# Keyboard.net
KiCad netlist of a schematic drawn in EAGLE
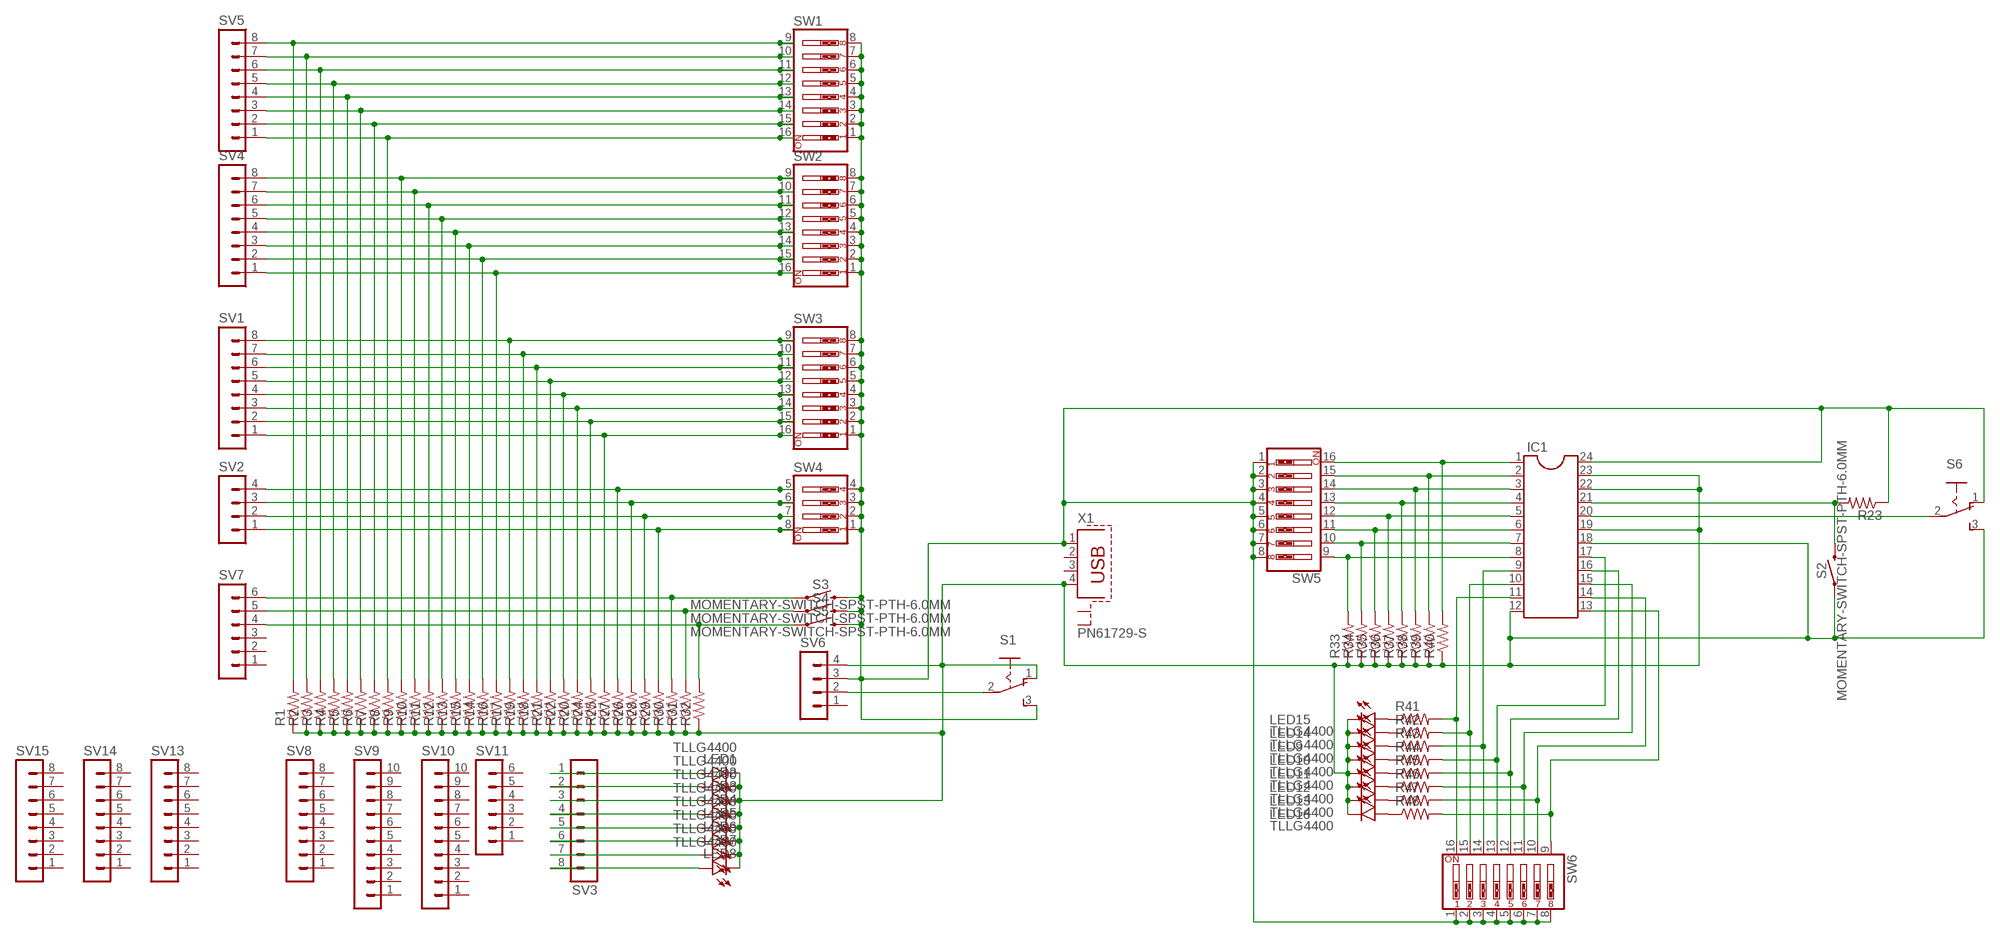
[diagram p0: schematic, sheet 1]

(export (version "E")
  (design (tool "Eeschema 10.0.6"))
  (components
    (comp (ref "IC1")
      (value "DIL24-6")
      (footprint "eagle-import:DIL24-6")
      (libsource (lib "eagle-import") (part "DIL24-6"))
    )
    (comp (ref "LED1")
      (value "TLLG4400")
      (footprint "eagle-import:LED3MM")
      (fields (field (name "MF") "VISHAY SEMICONDUCTOR"))
      (libsource (lib "eagle-import") (part "TLLG4400"))
    )
    (comp (ref "LED2")
      (value "TLLG4400")
      (footprint "eagle-import:LED3MM")
      (fields (field (name "MF") "VISHAY SEMICONDUCTOR"))
      (libsource (lib "eagle-import") (part "TLLG4400"))
    )
    (comp (ref "LED3")
      (value "TLLG4400")
      (footprint "eagle-import:LED3MM")
      (fields (field (name "MF") "VISHAY SEMICONDUCTOR"))
      (libsource (lib "eagle-import") (part "TLLG4400"))
    )
    (comp (ref "LED4")
      (value "TLLG4400")
      (footprint "eagle-import:LED3MM")
      (fields (field (name "MF") "VISHAY SEMICONDUCTOR"))
      (libsource (lib "eagle-import") (part "TLLG4400"))
    )
    (comp (ref "LED5")
      (value "TLLG4400")
      (footprint "eagle-import:LED3MM")
      (fields (field (name "MF") "VISHAY SEMICONDUCTOR"))
      (libsource (lib "eagle-import") (part "TLLG4400"))
    )
    (comp (ref "LED6")
      (value "TLLG4400")
      (footprint "eagle-import:LED3MM")
      (fields (field (name "MF") "VISHAY SEMICONDUCTOR"))
      (libsource (lib "eagle-import") (part "TLLG4400"))
    )
    (comp (ref "LED7")
      (value "TLLG4400")
      (footprint "eagle-import:LED3MM")
      (fields (field (name "MF") "VISHAY SEMICONDUCTOR"))
      (libsource (lib "eagle-import") (part "TLLG4400"))
    )
    (comp (ref "LED8")
      (value "TLLG4400")
      (footprint "eagle-import:LED3MM")
      (fields (field (name "MF") "VISHAY SEMICONDUCTOR"))
      (libsource (lib "eagle-import") (part "TLLG4400"))
    )
    (comp (ref "LED9")
      (value "TLLG4400")
      (footprint "eagle-import:LED3MM")
      (fields (field (name "MF") "VISHAY SEMICONDUCTOR"))
      (libsource (lib "eagle-import") (part "TLLG4400"))
    )
    (comp (ref "LED10")
      (value "TLLG4400")
      (footprint "eagle-import:LED3MM")
      (fields (field (name "MF") "VISHAY SEMICONDUCTOR"))
      (libsource (lib "eagle-import") (part "TLLG4400"))
    )
    (comp (ref "LED11")
      (value "TLLG4400")
      (footprint "eagle-import:LED3MM")
      (fields (field (name "MF") "VISHAY SEMICONDUCTOR"))
      (libsource (lib "eagle-import") (part "TLLG4400"))
    )
    (comp (ref "LED12")
      (value "TLLG4400")
      (footprint "eagle-import:LED3MM")
      (fields (field (name "MF") "VISHAY SEMICONDUCTOR"))
      (libsource (lib "eagle-import") (part "TLLG4400"))
    )
    (comp (ref "LED13")
      (value "TLLG4400")
      (footprint "eagle-import:LED3MM")
      (fields (field (name "MF") "VISHAY SEMICONDUCTOR"))
      (libsource (lib "eagle-import") (part "TLLG4400"))
    )
    (comp (ref "LED14")
      (value "TLLG4400")
      (footprint "eagle-import:LED3MM")
      (fields (field (name "MF") "VISHAY SEMICONDUCTOR"))
      (libsource (lib "eagle-import") (part "TLLG4400"))
    )
    (comp (ref "LED15")
      (value "TLLG4400")
      (footprint "eagle-import:LED3MM")
      (fields (field (name "MF") "VISHAY SEMICONDUCTOR"))
      (libsource (lib "eagle-import") (part "TLLG4400"))
    )
    (comp (ref "LED16")
      (value "TLLG4400")
      (footprint "eagle-import:LED3MM")
      (fields (field (name "MF") "VISHAY SEMICONDUCTOR"))
      (libsource (lib "eagle-import") (part "TLLG4400"))
    )
    (comp (ref "R1")
      (value "R-US_0207/2V")
      (footprint "eagle-import:0207_2V")
      (libsource (lib "eagle-import") (part "R-US_0207/2V"))
    )
    (comp (ref "R2")
      (value "R-US_0207/2V")
      (footprint "eagle-import:0207_2V")
      (libsource (lib "eagle-import") (part "R-US_0207/2V"))
    )
    (comp (ref "R3")
      (value "R-US_0207/2V")
      (footprint "eagle-import:0207_2V")
      (libsource (lib "eagle-import") (part "R-US_0207/2V"))
    )
    (comp (ref "R4")
      (value "R-US_0207/2V")
      (footprint "eagle-import:0207_2V")
      (libsource (lib "eagle-import") (part "R-US_0207/2V"))
    )
    (comp (ref "R5")
      (value "R-US_0207/2V")
      (footprint "eagle-import:0207_2V")
      (libsource (lib "eagle-import") (part "R-US_0207/2V"))
    )
    (comp (ref "R6")
      (value "R-US_0207/2V")
      (footprint "eagle-import:0207_2V")
      (libsource (lib "eagle-import") (part "R-US_0207/2V"))
    )
    (comp (ref "R7")
      (value "R-US_0207/2V")
      (footprint "eagle-import:0207_2V")
      (libsource (lib "eagle-import") (part "R-US_0207/2V"))
    )
    (comp (ref "R8")
      (value "R-US_0207/2V")
      (footprint "eagle-import:0207_2V")
      (libsource (lib "eagle-import") (part "R-US_0207/2V"))
    )
    (comp (ref "R9")
      (value "R-US_0207/2V")
      (footprint "eagle-import:0207_2V")
      (libsource (lib "eagle-import") (part "R-US_0207/2V"))
    )
    (comp (ref "R10")
      (value "R-US_0207/2V")
      (footprint "eagle-import:0207_2V")
      (libsource (lib "eagle-import") (part "R-US_0207/2V"))
    )
    (comp (ref "R11")
      (value "R-US_0207/2V")
      (footprint "eagle-import:0207_2V")
      (libsource (lib "eagle-import") (part "R-US_0207/2V"))
    )
    (comp (ref "R12")
      (value "R-US_0207/2V")
      (footprint "eagle-import:0207_2V")
      (libsource (lib "eagle-import") (part "R-US_0207/2V"))
    )
    (comp (ref "R13")
      (value "R-US_0207/2V")
      (footprint "eagle-import:0207_2V")
      (libsource (lib "eagle-import") (part "R-US_0207/2V"))
    )
    (comp (ref "R14")
      (value "R-US_0207/2V")
      (footprint "eagle-import:0207_2V")
      (libsource (lib "eagle-import") (part "R-US_0207/2V"))
    )
    (comp (ref "R15")
      (value "R-US_0207/2V")
      (footprint "eagle-import:0207_2V")
      (libsource (lib "eagle-import") (part "R-US_0207/2V"))
    )
    (comp (ref "R16")
      (value "R-US_0207/2V")
      (footprint "eagle-import:0207_2V")
      (libsource (lib "eagle-import") (part "R-US_0207/2V"))
    )
    (comp (ref "R17")
      (value "R-US_0207/2V")
      (footprint "eagle-import:0207_2V")
      (libsource (lib "eagle-import") (part "R-US_0207/2V"))
    )
    (comp (ref "R18")
      (value "R-US_0207/2V")
      (footprint "eagle-import:0207_2V")
      (libsource (lib "eagle-import") (part "R-US_0207/2V"))
    )
    (comp (ref "R19")
      (value "R-US_0207/2V")
      (footprint "eagle-import:0207_2V")
      (libsource (lib "eagle-import") (part "R-US_0207/2V"))
    )
    (comp (ref "R20")
      (value "R-US_0207/2V")
      (footprint "eagle-import:0207_2V")
      (libsource (lib "eagle-import") (part "R-US_0207/2V"))
    )
    (comp (ref "R21")
      (value "R-US_0207/2V")
      (footprint "eagle-import:0207_2V")
      (libsource (lib "eagle-import") (part "R-US_0207/2V"))
    )
    (comp (ref "R22")
      (value "R-US_0207/2V")
      (footprint "eagle-import:0207_2V")
      (libsource (lib "eagle-import") (part "R-US_0207/2V"))
    )
    (comp (ref "R23")
      (value "R-US_0207/2V")
      (footprint "eagle-import:0207_2V")
      (libsource (lib "eagle-import") (part "R-US_0207/2V"))
    )
    (comp (ref "R24")
      (value "R-US_0207/2V")
      (footprint "eagle-import:0207_2V")
      (libsource (lib "eagle-import") (part "R-US_0207/2V"))
    )
    (comp (ref "R25")
      (value "R-US_0207/2V")
      (footprint "eagle-import:0207_2V")
      (libsource (lib "eagle-import") (part "R-US_0207/2V"))
    )
    (comp (ref "R26")
      (value "R-US_0207/2V")
      (footprint "eagle-import:0207_2V")
      (libsource (lib "eagle-import") (part "R-US_0207/2V"))
    )
    (comp (ref "R27")
      (value "R-US_0207/2V")
      (footprint "eagle-import:0207_2V")
      (libsource (lib "eagle-import") (part "R-US_0207/2V"))
    )
    (comp (ref "R28")
      (value "R-US_0207/2V")
      (footprint "eagle-import:0207_2V")
      (libsource (lib "eagle-import") (part "R-US_0207/2V"))
    )
    (comp (ref "R29")
      (value "R-US_0207/2V")
      (footprint "eagle-import:0207_2V")
      (libsource (lib "eagle-import") (part "R-US_0207/2V"))
    )
    (comp (ref "R30")
      (value "R-US_0207/2V")
      (footprint "eagle-import:0207_2V")
      (libsource (lib "eagle-import") (part "R-US_0207/2V"))
    )
    (comp (ref "R31")
      (value "R-US_0207/2V")
      (footprint "eagle-import:0207_2V")
      (libsource (lib "eagle-import") (part "R-US_0207/2V"))
    )
    (comp (ref "R32")
      (value "R-US_0207/2V")
      (footprint "eagle-import:0207_2V")
      (libsource (lib "eagle-import") (part "R-US_0207/2V"))
    )
    (comp (ref "R33")
      (value "R-US_0207/2V")
      (footprint "eagle-import:0207_2V")
      (libsource (lib "eagle-import") (part "R-US_0207/2V"))
    )
    (comp (ref "R34")
      (value "R-US_0207/2V")
      (footprint "eagle-import:0207_2V")
      (libsource (lib "eagle-import") (part "R-US_0207/2V"))
    )
    (comp (ref "R35")
      (value "R-US_0207/2V")
      (footprint "eagle-import:0207_2V")
      (libsource (lib "eagle-import") (part "R-US_0207/2V"))
    )
    (comp (ref "R36")
      (value "R-US_0207/2V")
      (footprint "eagle-import:0207_2V")
      (libsource (lib "eagle-import") (part "R-US_0207/2V"))
    )
    (comp (ref "R37")
      (value "R-US_0207/2V")
      (footprint "eagle-import:0207_2V")
      (libsource (lib "eagle-import") (part "R-US_0207/2V"))
    )
    (comp (ref "R38")
      (value "R-US_0207/2V")
      (footprint "eagle-import:0207_2V")
      (libsource (lib "eagle-import") (part "R-US_0207/2V"))
    )
    (comp (ref "R39")
      (value "R-US_0207/2V")
      (footprint "eagle-import:0207_2V")
      (libsource (lib "eagle-import") (part "R-US_0207/2V"))
    )
    (comp (ref "R40")
      (value "R-US_0207/2V")
      (footprint "eagle-import:0207_2V")
      (libsource (lib "eagle-import") (part "R-US_0207/2V"))
    )
    (comp (ref "R41")
      (value "R-US_0207/2V")
      (footprint "eagle-import:0207_2V")
      (libsource (lib "eagle-import") (part "R-US_0207/2V"))
    )
    (comp (ref "R42")
      (value "R-US_0207/2V")
      (footprint "eagle-import:0207_2V")
      (libsource (lib "eagle-import") (part "R-US_0207/2V"))
    )
    (comp (ref "R43")
      (value "R-US_0207/2V")
      (footprint "eagle-import:0207_2V")
      (libsource (lib "eagle-import") (part "R-US_0207/2V"))
    )
    (comp (ref "R44")
      (value "R-US_0207/2V")
      (footprint "eagle-import:0207_2V")
      (libsource (lib "eagle-import") (part "R-US_0207/2V"))
    )
    (comp (ref "R45")
      (value "R-US_0207/2V")
      (footprint "eagle-import:0207_2V")
      (libsource (lib "eagle-import") (part "R-US_0207/2V"))
    )
    (comp (ref "R46")
      (value "R-US_0207/2V")
      (footprint "eagle-import:0207_2V")
      (libsource (lib "eagle-import") (part "R-US_0207/2V"))
    )
    (comp (ref "R47")
      (value "R-US_0207/2V")
      (footprint "eagle-import:0207_2V")
      (libsource (lib "eagle-import") (part "R-US_0207/2V"))
    )
    (comp (ref "R48")
      (value "R-US_0207/2V")
      (footprint "eagle-import:0207_2V")
      (libsource (lib "eagle-import") (part "R-US_0207/2V"))
    )
    (comp (ref "S1")
      (value "M251")
      (footprint "eagle-import:M251")
      (libsource (lib "eagle-import") (part "M251"))
    )
    (comp (ref "S2")
      (value "MOMENTARY-SWITCH-SPST-PTH-6.0MM")
      (footprint "eagle-import:TACTILE_SWITCH_PTH_6.0MM")
      (libsource (lib "eagle-import") (part "MOMENTARY-SWITCH-SPST-PTH-6.0MM"))
    )
    (comp (ref "S3")
      (value "MOMENTARY-SWITCH-SPST-PTH-6.0MM")
      (footprint "eagle-import:TACTILE_SWITCH_PTH_6.0MM")
      (libsource (lib "eagle-import") (part "MOMENTARY-SWITCH-SPST-PTH-6.0MM"))
    )
    (comp (ref "S4")
      (value "MOMENTARY-SWITCH-SPST-PTH-6.0MM")
      (footprint "eagle-import:TACTILE_SWITCH_PTH_6.0MM")
      (libsource (lib "eagle-import") (part "MOMENTARY-SWITCH-SPST-PTH-6.0MM"))
    )
    (comp (ref "S5")
      (value "MOMENTARY-SWITCH-SPST-PTH-6.0MM")
      (footprint "eagle-import:TACTILE_SWITCH_PTH_6.0MM")
      (libsource (lib "eagle-import") (part "MOMENTARY-SWITCH-SPST-PTH-6.0MM"))
    )
    (comp (ref "S6")
      (value "M251")
      (footprint "eagle-import:M251")
      (libsource (lib "eagle-import") (part "M251"))
    )
    (comp (ref "SV1")
      (value "MA08-1")
      (footprint "eagle-import:MA08-1")
      (libsource (lib "eagle-import") (part "MA08-1"))
    )
    (comp (ref "SV2")
      (value "MA04-1")
      (footprint "eagle-import:MA04-1")
      (libsource (lib "eagle-import") (part "MA04-1"))
    )
    (comp (ref "SV3")
      (value "MA08-1")
      (footprint "eagle-import:MA08-1")
      (libsource (lib "eagle-import") (part "MA08-1"))
    )
    (comp (ref "SV4")
      (value "MA08-1")
      (footprint "eagle-import:MA08-1")
      (libsource (lib "eagle-import") (part "MA08-1"))
    )
    (comp (ref "SV5")
      (value "MA08-1")
      (footprint "eagle-import:MA08-1")
      (libsource (lib "eagle-import") (part "MA08-1"))
    )
    (comp (ref "SV6")
      (value "MA04-1")
      (footprint "eagle-import:MA04-1")
      (libsource (lib "eagle-import") (part "MA04-1"))
    )
    (comp (ref "SV7")
      (value "MA06-1")
      (footprint "eagle-import:MA06-1")
      (libsource (lib "eagle-import") (part "MA06-1"))
    )
    (comp (ref "SV8")
      (value "MA08-1")
      (footprint "eagle-import:MA08-1")
      (libsource (lib "eagle-import") (part "MA08-1"))
    )
    (comp (ref "SV9")
      (value "MA10-1")
      (footprint "eagle-import:MA10-1")
      (libsource (lib "eagle-import") (part "MA10-1"))
    )
    (comp (ref "SV10")
      (value "MA10-1")
      (footprint "eagle-import:MA10-1")
      (libsource (lib "eagle-import") (part "MA10-1"))
    )
    (comp (ref "SV11")
      (value "MA06-1")
      (footprint "eagle-import:MA06-1")
      (libsource (lib "eagle-import") (part "MA06-1"))
    )
    (comp (ref "SV13")
      (value "MA08-1")
      (footprint "eagle-import:MA08-1")
      (libsource (lib "eagle-import") (part "MA08-1"))
    )
    (comp (ref "SV14")
      (value "MA08-1")
      (footprint "eagle-import:MA08-1")
      (libsource (lib "eagle-import") (part "MA08-1"))
    )
    (comp (ref "SV15")
      (value "MA08-1")
      (footprint "eagle-import:MA08-1")
      (libsource (lib "eagle-import") (part "MA08-1"))
    )
    (comp (ref "SW1")
      (value "SW_DIP-8")
      (footprint "eagle-import:EDG-08")
      (libsource (lib "eagle-import") (part "SW_DIP-8"))
    )
    (comp (ref "SW2")
      (value "SW_DIP-8")
      (footprint "eagle-import:EDG-08")
      (libsource (lib "eagle-import") (part "SW_DIP-8"))
    )
    (comp (ref "SW3")
      (value "SW_DIP-8")
      (footprint "eagle-import:EDG-08")
      (libsource (lib "eagle-import") (part "SW_DIP-8"))
    )
    (comp (ref "SW4")
      (value "SW_DIP-4")
      (footprint "eagle-import:EDG-04")
      (libsource (lib "eagle-import") (part "SW_DIP-4"))
    )
    (comp (ref "SW5")
      (value "SW_DIP-8")
      (footprint "eagle-import:EDG-08")
      (libsource (lib "eagle-import") (part "SW_DIP-8"))
    )
    (comp (ref "SW6")
      (value "SW_DIP-8")
      (footprint "eagle-import:EDG-08")
      (libsource (lib "eagle-import") (part "SW_DIP-8"))
    )
    (comp (ref "X1")
      (value "PN61729-S")
      (footprint "eagle-import:PN61729-S")
      (libsource (lib "eagle-import") (part "PN61729-S"))
    )
  )
  (nets
    (net (code "1") (name "Net-(IC1-Pad1)") (class "Default")
      (node (ref "IC1") (pin "1") (pinfunction "1_1") (pintype "passive"))
      (node (ref "R40") (pin "2") (pinfunction "2_2") (pintype "passive"))
      (node (ref "SW5") (pin "16") (pinfunction "16_16") (pintype "passive"))
    )
    (net (code "2") (name "Net-(IC1-Pad2)") (class "Default")
      (node (ref "IC1") (pin "2") (pinfunction "2_2") (pintype "passive"))
      (node (ref "R39") (pin "2") (pinfunction "2_2") (pintype "passive"))
      (node (ref "SW5") (pin "15") (pinfunction "15_15") (pintype "passive"))
    )
    (net (code "3") (name "Net-(IC1-Pad3)") (class "Default")
      (node (ref "IC1") (pin "3") (pinfunction "3_3") (pintype "passive"))
      (node (ref "R38") (pin "2") (pinfunction "2_2") (pintype "passive"))
      (node (ref "SW5") (pin "14") (pinfunction "14_14") (pintype "passive"))
    )
    (net (code "4") (name "Net-(IC1-Pad4)") (class "Default")
      (node (ref "IC1") (pin "4") (pinfunction "4_4") (pintype "passive"))
      (node (ref "R37") (pin "2") (pinfunction "2_2") (pintype "passive"))
      (node (ref "SW5") (pin "13") (pinfunction "13_13") (pintype "passive"))
    )
    (net (code "5") (name "Net-(IC1-Pad5)") (class "Default")
      (node (ref "IC1") (pin "5") (pinfunction "5_5") (pintype "passive"))
      (node (ref "R36") (pin "2") (pinfunction "2_2") (pintype "passive"))
      (node (ref "SW5") (pin "12") (pinfunction "12_12") (pintype "passive"))
    )
    (net (code "6") (name "Net-(IC1-Pad6)") (class "Default")
      (node (ref "IC1") (pin "6") (pinfunction "6_6") (pintype "passive"))
      (node (ref "R35") (pin "2") (pinfunction "2_2") (pintype "passive"))
      (node (ref "SW5") (pin "11") (pinfunction "11_11") (pintype "passive"))
    )
    (net (code "7") (name "Net-(IC1-Pad7)") (class "Default")
      (node (ref "IC1") (pin "7") (pinfunction "7_7") (pintype "passive"))
      (node (ref "R34") (pin "2") (pinfunction "2_2") (pintype "passive"))
      (node (ref "SW5") (pin "10") (pinfunction "10_10") (pintype "passive"))
    )
    (net (code "8") (name "Net-(IC1-Pad8)") (class "Default")
      (node (ref "IC1") (pin "8") (pinfunction "8_8") (pintype "passive"))
      (node (ref "R33") (pin "2") (pinfunction "2_2") (pintype "passive"))
      (node (ref "SW5") (pin "9") (pinfunction "9_9") (pintype "passive"))
    )
    (net (code "9") (name "Net-(IC1-Pad9)") (class "Default")
      (node (ref "IC1") (pin "9") (pinfunction "9_9") (pintype "passive"))
      (node (ref "R43") (pin "2") (pinfunction "2_2") (pintype "passive"))
      (node (ref "SW6") (pin "14") (pinfunction "14_14") (pintype "passive"))
    )
    (net (code "10") (name "Net-(IC1-Pad10)") (class "Default")
      (node (ref "IC1") (pin "10") (pinfunction "10_10") (pintype "passive"))
      (node (ref "R42") (pin "2") (pinfunction "2_2") (pintype "passive"))
      (node (ref "SW6") (pin "15") (pinfunction "15_15") (pintype "passive"))
    )
    (net (code "11") (name "Net-(IC1-Pad11)") (class "Default")
      (node (ref "IC1") (pin "11") (pinfunction "11_11") (pintype "passive"))
      (node (ref "R41") (pin "2") (pinfunction "2_2") (pintype "passive"))
      (node (ref "SW6") (pin "16") (pinfunction "16_16") (pintype "passive"))
    )
    (net (code "12") (name "Net-(IC1-Pad13)") (class "Default")
      (node (ref "IC1") (pin "13") (pinfunction "13_13") (pintype "passive"))
      (node (ref "R48") (pin "2") (pinfunction "2_2") (pintype "passive"))
      (node (ref "SW6") (pin "9") (pinfunction "9_9") (pintype "passive"))
    )
    (net (code "13") (name "Net-(IC1-Pad14)") (class "Default")
      (node (ref "IC1") (pin "14") (pinfunction "14_14") (pintype "passive"))
      (node (ref "R47") (pin "2") (pinfunction "2_2") (pintype "passive"))
      (node (ref "SW6") (pin "10") (pinfunction "10_10") (pintype "passive"))
    )
    (net (code "14") (name "Net-(IC1-Pad15)") (class "Default")
      (node (ref "IC1") (pin "15") (pinfunction "15_15") (pintype "passive"))
      (node (ref "R46") (pin "2") (pinfunction "2_2") (pintype "passive"))
      (node (ref "SW6") (pin "11") (pinfunction "11_11") (pintype "passive"))
    )
    (net (code "15") (name "Net-(IC1-Pad16)") (class "Default")
      (node (ref "IC1") (pin "16") (pinfunction "16_16") (pintype "passive"))
      (node (ref "R45") (pin "2") (pinfunction "2_2") (pintype "passive"))
      (node (ref "SW6") (pin "12") (pinfunction "12_12") (pintype "passive"))
    )
    (net (code "16") (name "Net-(IC1-Pad17)") (class "Default")
      (node (ref "IC1") (pin "17") (pinfunction "17_17") (pintype "passive"))
      (node (ref "R44") (pin "2") (pinfunction "2_2") (pintype "passive"))
      (node (ref "SW6") (pin "13") (pinfunction "13_13") (pintype "passive"))
    )
    (net (code "17") (name "Net-(LED1-C)") (class "Default")
      (node (ref "IC1") (pin "12") (pinfunction "12_12") (pintype "passive"))
      (node (ref "IC1") (pin "18") (pinfunction "18_18") (pintype "passive"))
      (node (ref "IC1") (pin "19") (pinfunction "19_19") (pintype "passive"))
      (node (ref "IC1") (pin "22") (pinfunction "22_22") (pintype "passive"))
      (node (ref "IC1") (pin "23") (pinfunction "23_23") (pintype "passive"))
      (node (ref "LED1") (pin "K") (pinfunction "C_K") (pintype "passive"))
      (node (ref "LED10") (pin "K") (pinfunction "C_K") (pintype "passive"))
      (node (ref "LED11") (pin "K") (pinfunction "C_K") (pintype "passive"))
      (node (ref "LED12") (pin "K") (pinfunction "C_K") (pintype "passive"))
      (node (ref "LED13") (pin "K") (pinfunction "C_K") (pintype "passive"))
      (node (ref "LED14") (pin "K") (pinfunction "C_K") (pintype "passive"))
      (node (ref "LED15") (pin "K") (pinfunction "C_K") (pintype "passive"))
      (node (ref "LED16") (pin "K") (pinfunction "C_K") (pintype "passive"))
      (node (ref "LED2") (pin "K") (pinfunction "C_K") (pintype "passive"))
      (node (ref "LED3") (pin "K") (pinfunction "C_K") (pintype "passive"))
      (node (ref "LED4") (pin "K") (pinfunction "C_K") (pintype "passive"))
      (node (ref "LED5") (pin "K") (pinfunction "C_K") (pintype "passive"))
      (node (ref "LED6") (pin "K") (pinfunction "C_K") (pintype "passive"))
      (node (ref "LED7") (pin "K") (pinfunction "C_K") (pintype "passive"))
      (node (ref "LED8") (pin "K") (pinfunction "C_K") (pintype "passive"))
      (node (ref "LED9") (pin "K") (pinfunction "C_K") (pintype "passive"))
      (node (ref "R1") (pin "1") (pinfunction "1_1") (pintype "passive"))
      (node (ref "R10") (pin "1") (pinfunction "1_1") (pintype "passive"))
      (node (ref "R11") (pin "1") (pinfunction "1_1") (pintype "passive"))
      (node (ref "R12") (pin "1") (pinfunction "1_1") (pintype "passive"))
      (node (ref "R13") (pin "1") (pinfunction "1_1") (pintype "passive"))
      (node (ref "R14") (pin "1") (pinfunction "1_1") (pintype "passive"))
      (node (ref "R15") (pin "1") (pinfunction "1_1") (pintype "passive"))
      (node (ref "R16") (pin "1") (pinfunction "1_1") (pintype "passive"))
      (node (ref "R17") (pin "1") (pinfunction "1_1") (pintype "passive"))
      (node (ref "R18") (pin "1") (pinfunction "1_1") (pintype "passive"))
      (node (ref "R19") (pin "1") (pinfunction "1_1") (pintype "passive"))
      (node (ref "R2") (pin "1") (pinfunction "1_1") (pintype "passive"))
      (node (ref "R20") (pin "1") (pinfunction "1_1") (pintype "passive"))
      (node (ref "R21") (pin "1") (pinfunction "1_1") (pintype "passive"))
      (node (ref "R22") (pin "1") (pinfunction "1_1") (pintype "passive"))
      (node (ref "R24") (pin "1") (pinfunction "1_1") (pintype "passive"))
      (node (ref "R25") (pin "1") (pinfunction "1_1") (pintype "passive"))
      (node (ref "R26") (pin "1") (pinfunction "1_1") (pintype "passive"))
      (node (ref "R27") (pin "1") (pinfunction "1_1") (pintype "passive"))
      (node (ref "R28") (pin "1") (pinfunction "1_1") (pintype "passive"))
      (node (ref "R29") (pin "1") (pinfunction "1_1") (pintype "passive"))
      (node (ref "R3") (pin "1") (pinfunction "1_1") (pintype "passive"))
      (node (ref "R30") (pin "1") (pinfunction "1_1") (pintype "passive"))
      (node (ref "R31") (pin "1") (pinfunction "1_1") (pintype "passive"))
      (node (ref "R32") (pin "1") (pinfunction "1_1") (pintype "passive"))
      (node (ref "R33") (pin "1") (pinfunction "1_1") (pintype "passive"))
      (node (ref "R34") (pin "1") (pinfunction "1_1") (pintype "passive"))
      (node (ref "R35") (pin "1") (pinfunction "1_1") (pintype "passive"))
      (node (ref "R36") (pin "1") (pinfunction "1_1") (pintype "passive"))
      (node (ref "R37") (pin "1") (pinfunction "1_1") (pintype "passive"))
      (node (ref "R38") (pin "1") (pinfunction "1_1") (pintype "passive"))
      (node (ref "R39") (pin "1") (pinfunction "1_1") (pintype "passive"))
      (node (ref "R4") (pin "1") (pinfunction "1_1") (pintype "passive"))
      (node (ref "R40") (pin "1") (pinfunction "1_1") (pintype "passive"))
      (node (ref "R5") (pin "1") (pinfunction "1_1") (pintype "passive"))
      (node (ref "R6") (pin "1") (pinfunction "1_1") (pintype "passive"))
      (node (ref "R7") (pin "1") (pinfunction "1_1") (pintype "passive"))
      (node (ref "R8") (pin "1") (pinfunction "1_1") (pintype "passive"))
      (node (ref "R9") (pin "1") (pinfunction "1_1") (pintype "passive"))
      (node (ref "S1") (pin "1") (pinfunction "O_1") (pintype "passive"))
      (node (ref "S2") (pin "1") (pinfunction "1_1") (pintype "passive"))
      (node (ref "S6") (pin "3") (pinfunction "S_3") (pintype "passive"))
      (node (ref "SV6") (pin "4") (pinfunction "4_4") (pintype "passive"))
      (node (ref "X1") (pin "4") (pinfunction "4_4") (pintype "passive"))
    )
    (net (code "18") (name "Net-(LED1-PadA)") (class "Default")
      (node (ref "LED1") (pin "A") (pinfunction "A_A") (pintype "passive"))
      (node (ref "SV3") (pin "1") (pinfunction "1_1") (pintype "passive"))
    )
    (net (code "19") (name "Net-(LED2-PadA)") (class "Default")
      (node (ref "LED2") (pin "A") (pinfunction "A_A") (pintype "passive"))
      (node (ref "SV3") (pin "2") (pinfunction "2_2") (pintype "passive"))
    )
    (net (code "20") (name "Net-(LED3-PadA)") (class "Default")
      (node (ref "LED3") (pin "A") (pinfunction "A_A") (pintype "passive"))
      (node (ref "SV3") (pin "3") (pinfunction "3_3") (pintype "passive"))
    )
    (net (code "21") (name "Net-(LED4-PadA)") (class "Default")
      (node (ref "LED4") (pin "A") (pinfunction "A_A") (pintype "passive"))
      (node (ref "SV3") (pin "4") (pinfunction "4_4") (pintype "passive"))
    )
    (net (code "22") (name "Net-(LED5-PadA)") (class "Default")
      (node (ref "LED5") (pin "A") (pinfunction "A_A") (pintype "passive"))
      (node (ref "SV3") (pin "5") (pinfunction "5_5") (pintype "passive"))
    )
    (net (code "23") (name "Net-(LED6-PadA)") (class "Default")
      (node (ref "LED6") (pin "A") (pinfunction "A_A") (pintype "passive"))
      (node (ref "SV3") (pin "6") (pinfunction "6_6") (pintype "passive"))
    )
    (net (code "24") (name "Net-(LED7-PadA)") (class "Default")
      (node (ref "LED7") (pin "A") (pinfunction "A_A") (pintype "passive"))
      (node (ref "SV3") (pin "7") (pinfunction "7_7") (pintype "passive"))
    )
    (net (code "25") (name "Net-(LED8-PadA)") (class "Default")
      (node (ref "LED8") (pin "A") (pinfunction "A_A") (pintype "passive"))
      (node (ref "SV3") (pin "8") (pinfunction "8_8") (pintype "passive"))
    )
    (net (code "26") (name "Net-(LED9-PadA)") (class "Default")
      (node (ref "LED9") (pin "A") (pinfunction "A_A") (pintype "passive"))
      (node (ref "R43") (pin "1") (pinfunction "1_1") (pintype "passive"))
    )
    (net (code "27") (name "Net-(LED10-PadA)") (class "Default")
      (node (ref "LED10") (pin "A") (pinfunction "A_A") (pintype "passive"))
      (node (ref "R44") (pin "1") (pinfunction "1_1") (pintype "passive"))
    )
    (net (code "28") (name "Net-(LED11-PadA)") (class "Default")
      (node (ref "LED11") (pin "A") (pinfunction "A_A") (pintype "passive"))
      (node (ref "R45") (pin "1") (pinfunction "1_1") (pintype "passive"))
    )
    (net (code "29") (name "Net-(LED12-PadA)") (class "Default")
      (node (ref "LED12") (pin "A") (pinfunction "A_A") (pintype "passive"))
      (node (ref "R46") (pin "1") (pinfunction "1_1") (pintype "passive"))
    )
    (net (code "30") (name "Net-(LED13-PadA)") (class "Default")
      (node (ref "LED13") (pin "A") (pinfunction "A_A") (pintype "passive"))
      (node (ref "R47") (pin "1") (pinfunction "1_1") (pintype "passive"))
    )
    (net (code "31") (name "Net-(LED14-PadA)") (class "Default")
      (node (ref "LED14") (pin "A") (pinfunction "A_A") (pintype "passive"))
      (node (ref "R42") (pin "1") (pinfunction "1_1") (pintype "passive"))
    )
    (net (code "32") (name "Net-(LED15-PadA)") (class "Default")
      (node (ref "LED15") (pin "A") (pinfunction "A_A") (pintype "passive"))
      (node (ref "R41") (pin "1") (pinfunction "1_1") (pintype "passive"))
    )
    (net (code "33") (name "Net-(LED16-PadA)") (class "Default")
      (node (ref "LED16") (pin "A") (pinfunction "A_A") (pintype "passive"))
      (node (ref "R48") (pin "1") (pinfunction "1_1") (pintype "passive"))
    )
    (net (code "34") (name "Net-(R1-Pad2)") (class "Default")
      (node (ref "R1") (pin "2") (pinfunction "2_2") (pintype "passive"))
      (node (ref "SV5") (pin "8") (pinfunction "8_8") (pintype "passive"))
      (node (ref "SW1") (pin "9") (pinfunction "9_9") (pintype "passive"))
    )
    (net (code "35") (name "Net-(R2-Pad2)") (class "Default")
      (node (ref "R2") (pin "2") (pinfunction "2_2") (pintype "passive"))
      (node (ref "SV5") (pin "7") (pinfunction "7_7") (pintype "passive"))
      (node (ref "SW1") (pin "10") (pinfunction "10_10") (pintype "passive"))
    )
    (net (code "36") (name "Net-(R3-Pad2)") (class "Default")
      (node (ref "R3") (pin "2") (pinfunction "2_2") (pintype "passive"))
      (node (ref "SV5") (pin "6") (pinfunction "6_6") (pintype "passive"))
      (node (ref "SW1") (pin "11") (pinfunction "11_11") (pintype "passive"))
    )
    (net (code "37") (name "Net-(R4-Pad2)") (class "Default")
      (node (ref "R4") (pin "2") (pinfunction "2_2") (pintype "passive"))
      (node (ref "SV5") (pin "5") (pinfunction "5_5") (pintype "passive"))
      (node (ref "SW1") (pin "12") (pinfunction "12_12") (pintype "passive"))
    )
    (net (code "38") (name "Net-(R5-Pad2)") (class "Default")
      (node (ref "R5") (pin "2") (pinfunction "2_2") (pintype "passive"))
      (node (ref "SV5") (pin "4") (pinfunction "4_4") (pintype "passive"))
      (node (ref "SW1") (pin "13") (pinfunction "13_13") (pintype "passive"))
    )
    (net (code "39") (name "Net-(R6-Pad2)") (class "Default")
      (node (ref "R6") (pin "2") (pinfunction "2_2") (pintype "passive"))
      (node (ref "SV5") (pin "3") (pinfunction "3_3") (pintype "passive"))
      (node (ref "SW1") (pin "14") (pinfunction "14_14") (pintype "passive"))
    )
    (net (code "40") (name "Net-(R7-Pad2)") (class "Default")
      (node (ref "R7") (pin "2") (pinfunction "2_2") (pintype "passive"))
      (node (ref "SV5") (pin "2") (pinfunction "2_2") (pintype "passive"))
      (node (ref "SW1") (pin "15") (pinfunction "15_15") (pintype "passive"))
    )
    (net (code "41") (name "Net-(R8-Pad2)") (class "Default")
      (node (ref "R8") (pin "2") (pinfunction "2_2") (pintype "passive"))
      (node (ref "SV5") (pin "1") (pinfunction "1_1") (pintype "passive"))
      (node (ref "SW1") (pin "16") (pinfunction "16_16") (pintype "passive"))
    )
    (net (code "42") (name "Net-(R9-Pad2)") (class "Default")
      (node (ref "R9") (pin "2") (pinfunction "2_2") (pintype "passive"))
      (node (ref "SV4") (pin "8") (pinfunction "8_8") (pintype "passive"))
      (node (ref "SW2") (pin "9") (pinfunction "9_9") (pintype "passive"))
    )
    (net (code "43") (name "Net-(R10-Pad2)") (class "Default")
      (node (ref "R10") (pin "2") (pinfunction "2_2") (pintype "passive"))
      (node (ref "SV4") (pin "7") (pinfunction "7_7") (pintype "passive"))
      (node (ref "SW2") (pin "10") (pinfunction "10_10") (pintype "passive"))
    )
    (net (code "44") (name "Net-(R11-Pad2)") (class "Default")
      (node (ref "R11") (pin "2") (pinfunction "2_2") (pintype "passive"))
      (node (ref "SV4") (pin "6") (pinfunction "6_6") (pintype "passive"))
      (node (ref "SW2") (pin "11") (pinfunction "11_11") (pintype "passive"))
    )
    (net (code "45") (name "Net-(R12-Pad2)") (class "Default")
      (node (ref "R12") (pin "2") (pinfunction "2_2") (pintype "passive"))
      (node (ref "SV4") (pin "5") (pinfunction "5_5") (pintype "passive"))
      (node (ref "SW2") (pin "12") (pinfunction "12_12") (pintype "passive"))
    )
    (net (code "46") (name "Net-(R13-Pad2)") (class "Default")
      (node (ref "R13") (pin "2") (pinfunction "2_2") (pintype "passive"))
      (node (ref "SV4") (pin "4") (pinfunction "4_4") (pintype "passive"))
      (node (ref "SW2") (pin "13") (pinfunction "13_13") (pintype "passive"))
    )
    (net (code "47") (name "Net-(R14-Pad2)") (class "Default")
      (node (ref "R14") (pin "2") (pinfunction "2_2") (pintype "passive"))
      (node (ref "SV4") (pin "2") (pinfunction "2_2") (pintype "passive"))
      (node (ref "SW2") (pin "15") (pinfunction "15_15") (pintype "passive"))
    )
    (net (code "48") (name "Net-(R15-Pad2)") (class "Default")
      (node (ref "R15") (pin "2") (pinfunction "2_2") (pintype "passive"))
      (node (ref "SV4") (pin "3") (pinfunction "3_3") (pintype "passive"))
      (node (ref "SW2") (pin "14") (pinfunction "14_14") (pintype "passive"))
    )
    (net (code "49") (name "Net-(R16-Pad2)") (class "Default")
      (node (ref "R16") (pin "2") (pinfunction "2_2") (pintype "passive"))
      (node (ref "SV4") (pin "1") (pinfunction "1_1") (pintype "passive"))
      (node (ref "SW2") (pin "16") (pinfunction "16_16") (pintype "passive"))
    )
    (net (code "50") (name "Net-(R17-Pad2)") (class "Default")
      (node (ref "R17") (pin "2") (pinfunction "2_2") (pintype "passive"))
      (node (ref "SV1") (pin "8") (pinfunction "8_8") (pintype "passive"))
      (node (ref "SW3") (pin "9") (pinfunction "9_9") (pintype "passive"))
    )
    (net (code "51") (name "Net-(R18-Pad2)") (class "Default")
      (node (ref "R18") (pin "2") (pinfunction "2_2") (pintype "passive"))
      (node (ref "SV1") (pin "6") (pinfunction "6_6") (pintype "passive"))
      (node (ref "SW3") (pin "11") (pinfunction "11_11") (pintype "passive"))
    )
    (net (code "52") (name "Net-(R19-Pad2)") (class "Default")
      (node (ref "R19") (pin "2") (pinfunction "2_2") (pintype "passive"))
      (node (ref "SV1") (pin "7") (pinfunction "7_7") (pintype "passive"))
      (node (ref "SW3") (pin "10") (pinfunction "10_10") (pintype "passive"))
    )
    (net (code "53") (name "Net-(R20-Pad2)") (class "Default")
      (node (ref "R20") (pin "2") (pinfunction "2_2") (pintype "passive"))
      (node (ref "SV1") (pin "3") (pinfunction "3_3") (pintype "passive"))
      (node (ref "SW3") (pin "14") (pinfunction "14_14") (pintype "passive"))
    )
    (net (code "54") (name "Net-(R21-Pad2)") (class "Default")
      (node (ref "R21") (pin "2") (pinfunction "2_2") (pintype "passive"))
      (node (ref "SV1") (pin "5") (pinfunction "5_5") (pintype "passive"))
      (node (ref "SW3") (pin "12") (pinfunction "12_12") (pintype "passive"))
    )
    (net (code "55") (name "Net-(R22-Pad2)") (class "Default")
      (node (ref "R22") (pin "2") (pinfunction "2_2") (pintype "passive"))
      (node (ref "SV1") (pin "4") (pinfunction "4_4") (pintype "passive"))
      (node (ref "SW3") (pin "13") (pinfunction "13_13") (pintype "passive"))
    )
    (net (code "56") (name "Net-(R24-Pad2)") (class "Default")
      (node (ref "R24") (pin "2") (pinfunction "2_2") (pintype "passive"))
      (node (ref "SV1") (pin "2") (pinfunction "2_2") (pintype "passive"))
      (node (ref "SW3") (pin "15") (pinfunction "15_15") (pintype "passive"))
    )
    (net (code "57") (name "Net-(R25-Pad2)") (class "Default")
      (node (ref "R25") (pin "2") (pinfunction "2_2") (pintype "passive"))
      (node (ref "SV1") (pin "1") (pinfunction "1_1") (pintype "passive"))
      (node (ref "SW3") (pin "16") (pinfunction "16_16") (pintype "passive"))
    )
    (net (code "58") (name "Net-(R26-Pad2)") (class "Default")
      (node (ref "R26") (pin "2") (pinfunction "2_2") (pintype "passive"))
      (node (ref "SV2") (pin "3") (pinfunction "3_3") (pintype "passive"))
      (node (ref "SW4") (pin "6") (pinfunction "6_6") (pintype "passive"))
    )
    (net (code "59") (name "Net-(R27-Pad2)") (class "Default")
      (node (ref "R27") (pin "2") (pinfunction "2_2") (pintype "passive"))
      (node (ref "SV2") (pin "4") (pinfunction "4_4") (pintype "passive"))
      (node (ref "SW4") (pin "5") (pinfunction "5_5") (pintype "passive"))
    )
    (net (code "60") (name "Net-(R28-Pad2)") (class "Default")
      (node (ref "R28") (pin "2") (pinfunction "2_2") (pintype "passive"))
      (node (ref "SV2") (pin "2") (pinfunction "2_2") (pintype "passive"))
      (node (ref "SW4") (pin "7") (pinfunction "7_7") (pintype "passive"))
    )
    (net (code "61") (name "Net-(R29-Pad2)") (class "Default")
      (node (ref "R29") (pin "2") (pinfunction "2_2") (pintype "passive"))
      (node (ref "SV2") (pin "1") (pinfunction "1_1") (pintype "passive"))
      (node (ref "SW4") (pin "8") (pinfunction "8_8") (pintype "passive"))
    )
    (net (code "62") (name "Net-(R30-Pad2)") (class "Default")
      (node (ref "R30") (pin "2") (pinfunction "2_2") (pintype "passive"))
      (node (ref "S3") (pin "1") (pinfunction "1_1") (pintype "passive"))
      (node (ref "SV7") (pin "6") (pinfunction "6_6") (pintype "passive"))
    )
    (net (code "63") (name "Net-(R31-Pad2)") (class "Default")
      (node (ref "R31") (pin "2") (pinfunction "2_2") (pintype "passive"))
      (node (ref "S4") (pin "1") (pinfunction "1_1") (pintype "passive"))
      (node (ref "SV7") (pin "5") (pinfunction "5_5") (pintype "passive"))
    )
    (net (code "64") (name "Net-(R32-Pad2)") (class "Default")
      (node (ref "R32") (pin "2") (pinfunction "2_2") (pintype "passive"))
      (node (ref "S5") (pin "1") (pinfunction "1_1") (pintype "passive"))
      (node (ref "SV7") (pin "4") (pinfunction "4_4") (pintype "passive"))
    )
    (net (code "65") (name "Net-(S1-P)") (class "Default")
      (node (ref "S1") (pin "2") (pinfunction "P_2") (pintype "passive"))
      (node (ref "SV6") (pin "2") (pinfunction "2_2") (pintype "passive"))
    )
    (net (code "66") (name "Net-(S1-S)") (class "Default")
      (node (ref "IC1") (pin "24") (pinfunction "24_24") (pintype "passive"))
      (node (ref "R23") (pin "1") (pinfunction "1_1") (pintype "passive"))
      (node (ref "S1") (pin "3") (pinfunction "S_3") (pintype "passive"))
      (node (ref "S3") (pin "3") (pinfunction "2_3") (pintype "passive"))
      (node (ref "S4") (pin "3") (pinfunction "2_3") (pintype "passive"))
      (node (ref "S5") (pin "3") (pinfunction "2_3") (pintype "passive"))
      (node (ref "S6") (pin "1") (pinfunction "O_1") (pintype "passive"))
      (node (ref "SV6") (pin "3") (pinfunction "3_3") (pintype "passive"))
      (node (ref "SW1") (pin "1") (pinfunction "1_1") (pintype "passive"))
      (node (ref "SW1") (pin "2") (pinfunction "2_2") (pintype "passive"))
      (node (ref "SW1") (pin "3") (pinfunction "3_3") (pintype "passive"))
      (node (ref "SW1") (pin "4") (pinfunction "4_4") (pintype "passive"))
      (node (ref "SW1") (pin "5") (pinfunction "5_5") (pintype "passive"))
      (node (ref "SW1") (pin "6") (pinfunction "6_6") (pintype "passive"))
      (node (ref "SW1") (pin "7") (pinfunction "7_7") (pintype "passive"))
      (node (ref "SW1") (pin "8") (pinfunction "8_8") (pintype "passive"))
      (node (ref "SW2") (pin "1") (pinfunction "1_1") (pintype "passive"))
      (node (ref "SW2") (pin "2") (pinfunction "2_2") (pintype "passive"))
      (node (ref "SW2") (pin "3") (pinfunction "3_3") (pintype "passive"))
      (node (ref "SW2") (pin "4") (pinfunction "4_4") (pintype "passive"))
      (node (ref "SW2") (pin "5") (pinfunction "5_5") (pintype "passive"))
      (node (ref "SW2") (pin "6") (pinfunction "6_6") (pintype "passive"))
      (node (ref "SW2") (pin "7") (pinfunction "7_7") (pintype "passive"))
      (node (ref "SW2") (pin "8") (pinfunction "8_8") (pintype "passive"))
      (node (ref "SW3") (pin "1") (pinfunction "1_1") (pintype "passive"))
      (node (ref "SW3") (pin "2") (pinfunction "2_2") (pintype "passive"))
      (node (ref "SW3") (pin "3") (pinfunction "3_3") (pintype "passive"))
      (node (ref "SW3") (pin "4") (pinfunction "4_4") (pintype "passive"))
      (node (ref "SW3") (pin "5") (pinfunction "5_5") (pintype "passive"))
      (node (ref "SW3") (pin "6") (pinfunction "6_6") (pintype "passive"))
      (node (ref "SW3") (pin "7") (pinfunction "7_7") (pintype "passive"))
      (node (ref "SW3") (pin "8") (pinfunction "8_8") (pintype "passive"))
      (node (ref "SW4") (pin "1") (pinfunction "1_1") (pintype "passive"))
      (node (ref "SW4") (pin "2") (pinfunction "2_2") (pintype "passive"))
      (node (ref "SW4") (pin "3") (pinfunction "3_3") (pintype "passive"))
      (node (ref "SW4") (pin "4") (pinfunction "4_4") (pintype "passive"))
      (node (ref "SW5") (pin "1") (pinfunction "1_1") (pintype "passive"))
      (node (ref "SW5") (pin "2") (pinfunction "2_2") (pintype "passive"))
      (node (ref "SW5") (pin "3") (pinfunction "3_3") (pintype "passive"))
      (node (ref "SW5") (pin "4") (pinfunction "4_4") (pintype "passive"))
      (node (ref "SW5") (pin "5") (pinfunction "5_5") (pintype "passive"))
      (node (ref "SW5") (pin "6") (pinfunction "6_6") (pintype "passive"))
      (node (ref "SW5") (pin "7") (pinfunction "7_7") (pintype "passive"))
      (node (ref "SW5") (pin "8") (pinfunction "8_8") (pintype "passive"))
      (node (ref "SW6") (pin "1") (pinfunction "1_1") (pintype "passive"))
      (node (ref "SW6") (pin "2") (pinfunction "2_2") (pintype "passive"))
      (node (ref "SW6") (pin "3") (pinfunction "3_3") (pintype "passive"))
      (node (ref "SW6") (pin "4") (pinfunction "4_4") (pintype "passive"))
      (node (ref "SW6") (pin "5") (pinfunction "5_5") (pintype "passive"))
      (node (ref "SW6") (pin "6") (pinfunction "6_6") (pintype "passive"))
      (node (ref "SW6") (pin "7") (pinfunction "7_7") (pintype "passive"))
      (node (ref "SW6") (pin "8") (pinfunction "8_8") (pintype "passive"))
      (node (ref "X1") (pin "1") (pinfunction "1_1") (pintype "passive"))
    )
    (net (code "67") (name "Net-(S2-2)") (class "Default")
      (node (ref "IC1") (pin "21") (pinfunction "21_21") (pintype "passive"))
      (node (ref "R23") (pin "2") (pinfunction "2_2") (pintype "passive"))
      (node (ref "S2") (pin "3") (pinfunction "2_3") (pintype "passive"))
    )
    (net (code "68") (name "Net-(S6-P)") (class "Default")
      (node (ref "IC1") (pin "20") (pinfunction "20_20") (pintype "passive"))
      (node (ref "S6") (pin "2") (pinfunction "P_2") (pintype "passive"))
    )
    (net (code "69") (name "unconnected-(SV6-Pad1)") (class "Default")
      (node (ref "SV6") (pin "1") (pinfunction "1_1") (pintype "passive"))
    )
    (net (code "70") (name "unconnected-(SV7-Pad1)") (class "Default")
      (node (ref "SV7") (pin "1") (pinfunction "1_1") (pintype "passive"))
    )
    (net (code "71") (name "unconnected-(SV7-Pad2)") (class "Default")
      (node (ref "SV7") (pin "2") (pinfunction "2_2") (pintype "passive"))
    )
    (net (code "72") (name "unconnected-(SV7-Pad3)") (class "Default")
      (node (ref "SV7") (pin "3") (pinfunction "3_3") (pintype "passive"))
    )
    (net (code "73") (name "unconnected-(SV8-Pad1)") (class "Default")
      (node (ref "SV8") (pin "1") (pinfunction "1_1") (pintype "passive"))
    )
    (net (code "74") (name "unconnected-(SV8-Pad2)") (class "Default")
      (node (ref "SV8") (pin "2") (pinfunction "2_2") (pintype "passive"))
    )
    (net (code "75") (name "unconnected-(SV8-Pad3)") (class "Default")
      (node (ref "SV8") (pin "3") (pinfunction "3_3") (pintype "passive"))
    )
    (net (code "76") (name "unconnected-(SV8-Pad4)") (class "Default")
      (node (ref "SV8") (pin "4") (pinfunction "4_4") (pintype "passive"))
    )
    (net (code "77") (name "unconnected-(SV8-Pad5)") (class "Default")
      (node (ref "SV8") (pin "5") (pinfunction "5_5") (pintype "passive"))
    )
    (net (code "78") (name "unconnected-(SV8-Pad6)") (class "Default")
      (node (ref "SV8") (pin "6") (pinfunction "6_6") (pintype "passive"))
    )
    (net (code "79") (name "unconnected-(SV8-Pad7)") (class "Default")
      (node (ref "SV8") (pin "7") (pinfunction "7_7") (pintype "passive"))
    )
    (net (code "80") (name "unconnected-(SV8-Pad8)") (class "Default")
      (node (ref "SV8") (pin "8") (pinfunction "8_8") (pintype "passive"))
    )
    (net (code "81") (name "unconnected-(SV9-Pad1)") (class "Default")
      (node (ref "SV9") (pin "1") (pinfunction "1_1") (pintype "passive"))
    )
    (net (code "82") (name "unconnected-(SV9-Pad2)") (class "Default")
      (node (ref "SV9") (pin "2") (pinfunction "2_2") (pintype "passive"))
    )
    (net (code "83") (name "unconnected-(SV9-Pad3)") (class "Default")
      (node (ref "SV9") (pin "3") (pinfunction "3_3") (pintype "passive"))
    )
    (net (code "84") (name "unconnected-(SV9-Pad4)") (class "Default")
      (node (ref "SV9") (pin "4") (pinfunction "4_4") (pintype "passive"))
    )
    (net (code "85") (name "unconnected-(SV9-Pad5)") (class "Default")
      (node (ref "SV9") (pin "5") (pinfunction "5_5") (pintype "passive"))
    )
    (net (code "86") (name "unconnected-(SV9-Pad6)") (class "Default")
      (node (ref "SV9") (pin "6") (pinfunction "6_6") (pintype "passive"))
    )
    (net (code "87") (name "unconnected-(SV9-Pad7)") (class "Default")
      (node (ref "SV9") (pin "7") (pinfunction "7_7") (pintype "passive"))
    )
    (net (code "88") (name "unconnected-(SV9-Pad8)") (class "Default")
      (node (ref "SV9") (pin "8") (pinfunction "8_8") (pintype "passive"))
    )
    (net (code "89") (name "unconnected-(SV9-Pad9)") (class "Default")
      (node (ref "SV9") (pin "9") (pinfunction "9_9") (pintype "passive"))
    )
    (net (code "90") (name "unconnected-(SV9-Pad10)") (class "Default")
      (node (ref "SV9") (pin "10") (pinfunction "10_10") (pintype "passive"))
    )
    (net (code "91") (name "unconnected-(SV10-Pad1)") (class "Default")
      (node (ref "SV10") (pin "1") (pinfunction "1_1") (pintype "passive"))
    )
    (net (code "92") (name "unconnected-(SV10-Pad2)") (class "Default")
      (node (ref "SV10") (pin "2") (pinfunction "2_2") (pintype "passive"))
    )
    (net (code "93") (name "unconnected-(SV10-Pad3)") (class "Default")
      (node (ref "SV10") (pin "3") (pinfunction "3_3") (pintype "passive"))
    )
    (net (code "94") (name "unconnected-(SV10-Pad4)") (class "Default")
      (node (ref "SV10") (pin "4") (pinfunction "4_4") (pintype "passive"))
    )
    (net (code "95") (name "unconnected-(SV10-Pad5)") (class "Default")
      (node (ref "SV10") (pin "5") (pinfunction "5_5") (pintype "passive"))
    )
    (net (code "96") (name "unconnected-(SV10-Pad6)") (class "Default")
      (node (ref "SV10") (pin "6") (pinfunction "6_6") (pintype "passive"))
    )
    (net (code "97") (name "unconnected-(SV10-Pad7)") (class "Default")
      (node (ref "SV10") (pin "7") (pinfunction "7_7") (pintype "passive"))
    )
    (net (code "98") (name "unconnected-(SV10-Pad8)") (class "Default")
      (node (ref "SV10") (pin "8") (pinfunction "8_8") (pintype "passive"))
    )
    (net (code "99") (name "unconnected-(SV10-Pad9)") (class "Default")
      (node (ref "SV10") (pin "9") (pinfunction "9_9") (pintype "passive"))
    )
    (net (code "100") (name "unconnected-(SV10-Pad10)") (class "Default")
      (node (ref "SV10") (pin "10") (pinfunction "10_10") (pintype "passive"))
    )
    (net (code "101") (name "unconnected-(SV11-Pad1)") (class "Default")
      (node (ref "SV11") (pin "1") (pinfunction "1_1") (pintype "passive"))
    )
    (net (code "102") (name "unconnected-(SV11-Pad2)") (class "Default")
      (node (ref "SV11") (pin "2") (pinfunction "2_2") (pintype "passive"))
    )
    (net (code "103") (name "unconnected-(SV11-Pad3)") (class "Default")
      (node (ref "SV11") (pin "3") (pinfunction "3_3") (pintype "passive"))
    )
    (net (code "104") (name "unconnected-(SV11-Pad4)") (class "Default")
      (node (ref "SV11") (pin "4") (pinfunction "4_4") (pintype "passive"))
    )
    (net (code "105") (name "unconnected-(SV11-Pad5)") (class "Default")
      (node (ref "SV11") (pin "5") (pinfunction "5_5") (pintype "passive"))
    )
    (net (code "106") (name "unconnected-(SV11-Pad6)") (class "Default")
      (node (ref "SV11") (pin "6") (pinfunction "6_6") (pintype "passive"))
    )
    (net (code "107") (name "unconnected-(SV13-Pad1)") (class "Default")
      (node (ref "SV13") (pin "1") (pinfunction "1_1") (pintype "passive"))
    )
    (net (code "108") (name "unconnected-(SV13-Pad2)") (class "Default")
      (node (ref "SV13") (pin "2") (pinfunction "2_2") (pintype "passive"))
    )
    (net (code "109") (name "unconnected-(SV13-Pad3)") (class "Default")
      (node (ref "SV13") (pin "3") (pinfunction "3_3") (pintype "passive"))
    )
    (net (code "110") (name "unconnected-(SV13-Pad4)") (class "Default")
      (node (ref "SV13") (pin "4") (pinfunction "4_4") (pintype "passive"))
    )
    (net (code "111") (name "unconnected-(SV13-Pad5)") (class "Default")
      (node (ref "SV13") (pin "5") (pinfunction "5_5") (pintype "passive"))
    )
    (net (code "112") (name "unconnected-(SV13-Pad6)") (class "Default")
      (node (ref "SV13") (pin "6") (pinfunction "6_6") (pintype "passive"))
    )
    (net (code "113") (name "unconnected-(SV13-Pad7)") (class "Default")
      (node (ref "SV13") (pin "7") (pinfunction "7_7") (pintype "passive"))
    )
    (net (code "114") (name "unconnected-(SV13-Pad8)") (class "Default")
      (node (ref "SV13") (pin "8") (pinfunction "8_8") (pintype "passive"))
    )
    (net (code "115") (name "unconnected-(SV14-Pad1)") (class "Default")
      (node (ref "SV14") (pin "1") (pinfunction "1_1") (pintype "passive"))
    )
    (net (code "116") (name "unconnected-(SV14-Pad2)") (class "Default")
      (node (ref "SV14") (pin "2") (pinfunction "2_2") (pintype "passive"))
    )
    (net (code "117") (name "unconnected-(SV14-Pad3)") (class "Default")
      (node (ref "SV14") (pin "3") (pinfunction "3_3") (pintype "passive"))
    )
    (net (code "118") (name "unconnected-(SV14-Pad4)") (class "Default")
      (node (ref "SV14") (pin "4") (pinfunction "4_4") (pintype "passive"))
    )
    (net (code "119") (name "unconnected-(SV14-Pad5)") (class "Default")
      (node (ref "SV14") (pin "5") (pinfunction "5_5") (pintype "passive"))
    )
    (net (code "120") (name "unconnected-(SV14-Pad6)") (class "Default")
      (node (ref "SV14") (pin "6") (pinfunction "6_6") (pintype "passive"))
    )
    (net (code "121") (name "unconnected-(SV14-Pad7)") (class "Default")
      (node (ref "SV14") (pin "7") (pinfunction "7_7") (pintype "passive"))
    )
    (net (code "122") (name "unconnected-(SV14-Pad8)") (class "Default")
      (node (ref "SV14") (pin "8") (pinfunction "8_8") (pintype "passive"))
    )
    (net (code "123") (name "unconnected-(SV15-Pad1)") (class "Default")
      (node (ref "SV15") (pin "1") (pinfunction "1_1") (pintype "passive"))
    )
    (net (code "124") (name "unconnected-(SV15-Pad2)") (class "Default")
      (node (ref "SV15") (pin "2") (pinfunction "2_2") (pintype "passive"))
    )
    (net (code "125") (name "unconnected-(SV15-Pad3)") (class "Default")
      (node (ref "SV15") (pin "3") (pinfunction "3_3") (pintype "passive"))
    )
    (net (code "126") (name "unconnected-(SV15-Pad4)") (class "Default")
      (node (ref "SV15") (pin "4") (pinfunction "4_4") (pintype "passive"))
    )
    (net (code "127") (name "unconnected-(SV15-Pad5)") (class "Default")
      (node (ref "SV15") (pin "5") (pinfunction "5_5") (pintype "passive"))
    )
    (net (code "128") (name "unconnected-(SV15-Pad6)") (class "Default")
      (node (ref "SV15") (pin "6") (pinfunction "6_6") (pintype "passive"))
    )
    (net (code "129") (name "unconnected-(SV15-Pad7)") (class "Default")
      (node (ref "SV15") (pin "7") (pinfunction "7_7") (pintype "passive"))
    )
    (net (code "130") (name "unconnected-(SV15-Pad8)") (class "Default")
      (node (ref "SV15") (pin "8") (pinfunction "8_8") (pintype "passive"))
    )
    (net (code "131") (name "unconnected-(X1-Pad2)") (class "Default")
      (node (ref "X1") (pin "2") (pinfunction "2_2") (pintype "passive"))
    )
    (net (code "132") (name "unconnected-(X1-Pad3)") (class "Default")
      (node (ref "X1") (pin "3") (pinfunction "3_3") (pintype "passive"))
    )
    (net (code "133") (name "unconnected-(X1-PadS1)") (class "Default")
      (node (ref "X1") (pin "S1") (pinfunction "S1_S1") (pintype "passive"))
    )
    (net (code "134") (name "unconnected-(X1-PadS2)") (class "Default")
      (node (ref "X1") (pin "S2") (pinfunction "S2_S2") (pintype "passive"))
    )
  )
)
